# insulated_rectifier.net
KiCad netlist of a schematic drawn in Altium Designer
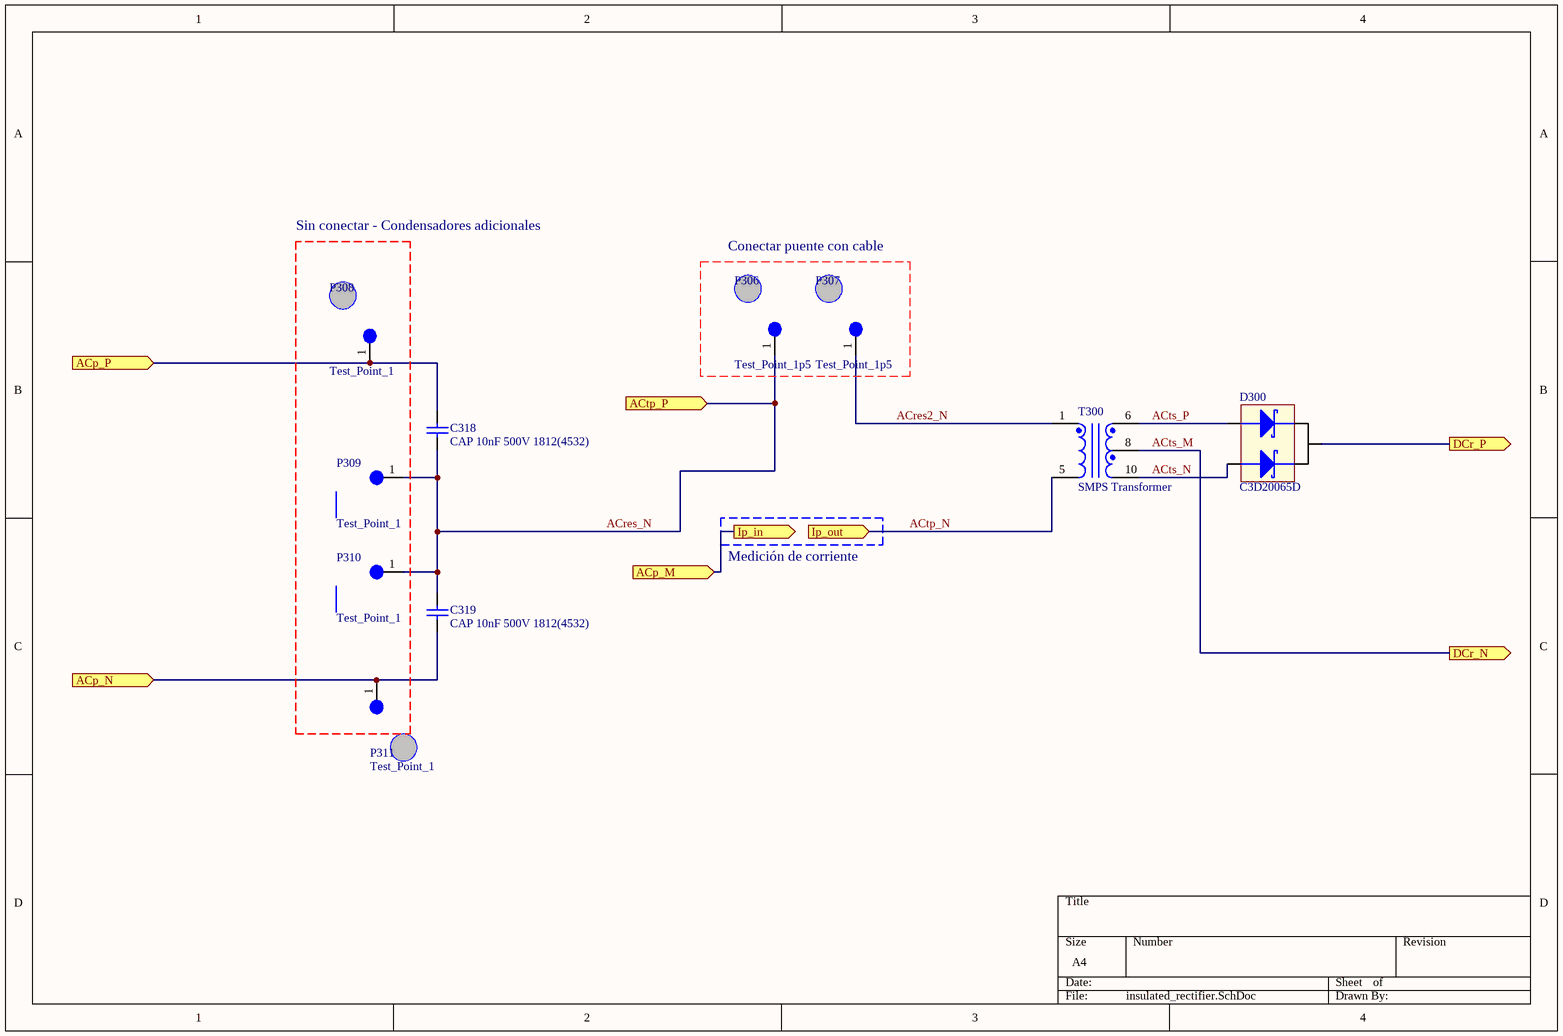
[diagram p0: insulated_rectifier.SchDoc]

(export (version "E")
  (design (tool "Eeschema 10.0.6"))
  (components
    (comp (ref "C318")
      (value "CAP 10nF 500V 1812(4532)")
      (footprint "CAPC1812(4532)230_M")
      (description "CAP 10nF 500V ±10% 1812 (4532 Metric) Thickness 2.3mm SMD")
      (fields (field (name "TOLERANCE") "Â±10%"))
      (libsource (lib "Altium Content Vault") (part "CAP"))
    )
    (comp (ref "C319")
      (value "CAP 10nF 500V 1812(4532)")
      (footprint "CAPC1812(4532)230_M")
      (description "CAP 10nF 500V ±10% 1812 (4532 Metric) Thickness 2.3mm SMD")
      (fields (field (name "TOLERANCE") "Â±10%"))
      (libsource (lib "Altium Content Vault") (part "CAP"))
    )
    (comp (ref "D300")
      (value "C3D20065D")
      (footprint "TO-247-3_hsa")
      (description "Schottky Diodes & Rectifiers Schottky Diode 2X10A, 650V C3D20065D")
      (fields (field (name "MANUFACTURER") "Cree"))
      (libsource (lib "SUBBOARD-power_stage") (part "C3D20065D"))
    )
    (comp (ref "P306")
      (value "Test_Point_1p5")
      (footprint "_TP_1p5")
      (description "Test point 1.5mm")
      (libsource (lib "Altium_Library_POWERLAB") (part "Test_Point_1p5"))
    )
    (comp (ref "P307")
      (value "Test_Point_1p5")
      (footprint "_TP_1p5")
      (description "Test point 1.5mm")
      (libsource (lib "Altium_Library_POWERLAB") (part "Test_Point_1p5"))
    )
    (comp (ref "P308")
      (value "Test_Point_1")
      (footprint "_TP_1mm")
      (description "Test point 1mm")
      (libsource (lib "") (part "Test_Point_1_1"))
    )
    (comp (ref "P309")
      (value "Test_Point_1")
      (footprint "_TP_1mm")
      (description "Test point 1mm")
      (libsource (lib "Altium_Library_POWERLAB") (part "Test_Point_1"))
    )
    (comp (ref "P310")
      (value "Test_Point_1")
      (footprint "_TP_1mm")
      (description "Test point 1mm")
      (libsource (lib "Altium_Library_POWERLAB") (part "Test_Point_1"))
    )
    (comp (ref "P311")
      (value "Test_Point_1")
      (footprint "_TP_1mm")
      (description "Test point 1mm")
      (libsource (lib "") (part "Test_Point_1_2"))
    )
    (comp (ref "T300")
      (value "SMPS Transformer")
      (footprint "Payton_SMPS_trafo_61446")
      (description "1400W SMPS Transformer Payton 61446")
      (libsource (lib "Altium_Library_POWERLAB") (part "Payton_SMPS_trafo_61446"))
    )
  )
  (nets
    (net (code "2") (name "/ACp_N") (class "Default")
      (node (ref "C319") (pin "1") (pinfunction "1_1") (pintype "passive"))
      (node (ref "P311") (pin "1") (pinfunction "1_1") (pintype "passive"))
    )
    (net (code "3") (name "/ACp_P") (class "Default")
      (node (ref "C318") (pin "2") (pinfunction "2_2") (pintype "passive"))
      (node (ref "P308") (pin "1") (pinfunction "1_1") (pintype "passive"))
    )
    (net (code "4") (name "/ACres2_N") (class "Default")
      (node (ref "P307") (pin "1") (pinfunction "1_1") (pintype "passive"))
      (node (ref "T300") (pin "1") (pinfunction "0_1") (pintype "passive"))
    )
    (net (code "5") (name "/ACres_N") (class "Default")
      (node (ref "C318") (pin "1") (pinfunction "1_1") (pintype "passive"))
      (node (ref "C319") (pin "2") (pinfunction "2_2") (pintype "passive"))
      (node (ref "P306") (pin "1") (pinfunction "1_1") (pintype "passive"))
      (node (ref "P309") (pin "1") (pinfunction "1_1") (pintype "passive"))
      (node (ref "P310") (pin "1") (pinfunction "1_1") (pintype "passive"))
    )
    (net (code "6") (name "/ACtp_N") (class "Default")
      (node (ref "T300") (pin "5") (pinfunction "1_5") (pintype "passive"))
    )
    (net (code "7") (name "/ACts_M") (class "Default")
      (node (ref "T300") (pin "8") (pinfunction "6_8") (pintype "passive"))
    )
    (net (code "8") (name "/ACts_N") (class "Default")
      (node (ref "D300") (pin "3") (pinfunction "14_3") (pintype "passive"))
      (node (ref "T300") (pin "10") (pinfunction "0_10") (pintype "passive"))
    )
    (net (code "9") (name "/ACts_P") (class "Default")
      (node (ref "D300") (pin "1") (pinfunction "14_1") (pintype "passive"))
      (node (ref "T300") (pin "6") (pinfunction "1_6") (pintype "passive"))
    )
    (net (code "10") (name "/DCr_P") (class "Default")
      (node (ref "D300") (pin "2") (pinfunction "15_2") (pintype "passive"))
    )
  )
)
